# Display.net
KiCad netlist of a schematic drawn in Altium Designer
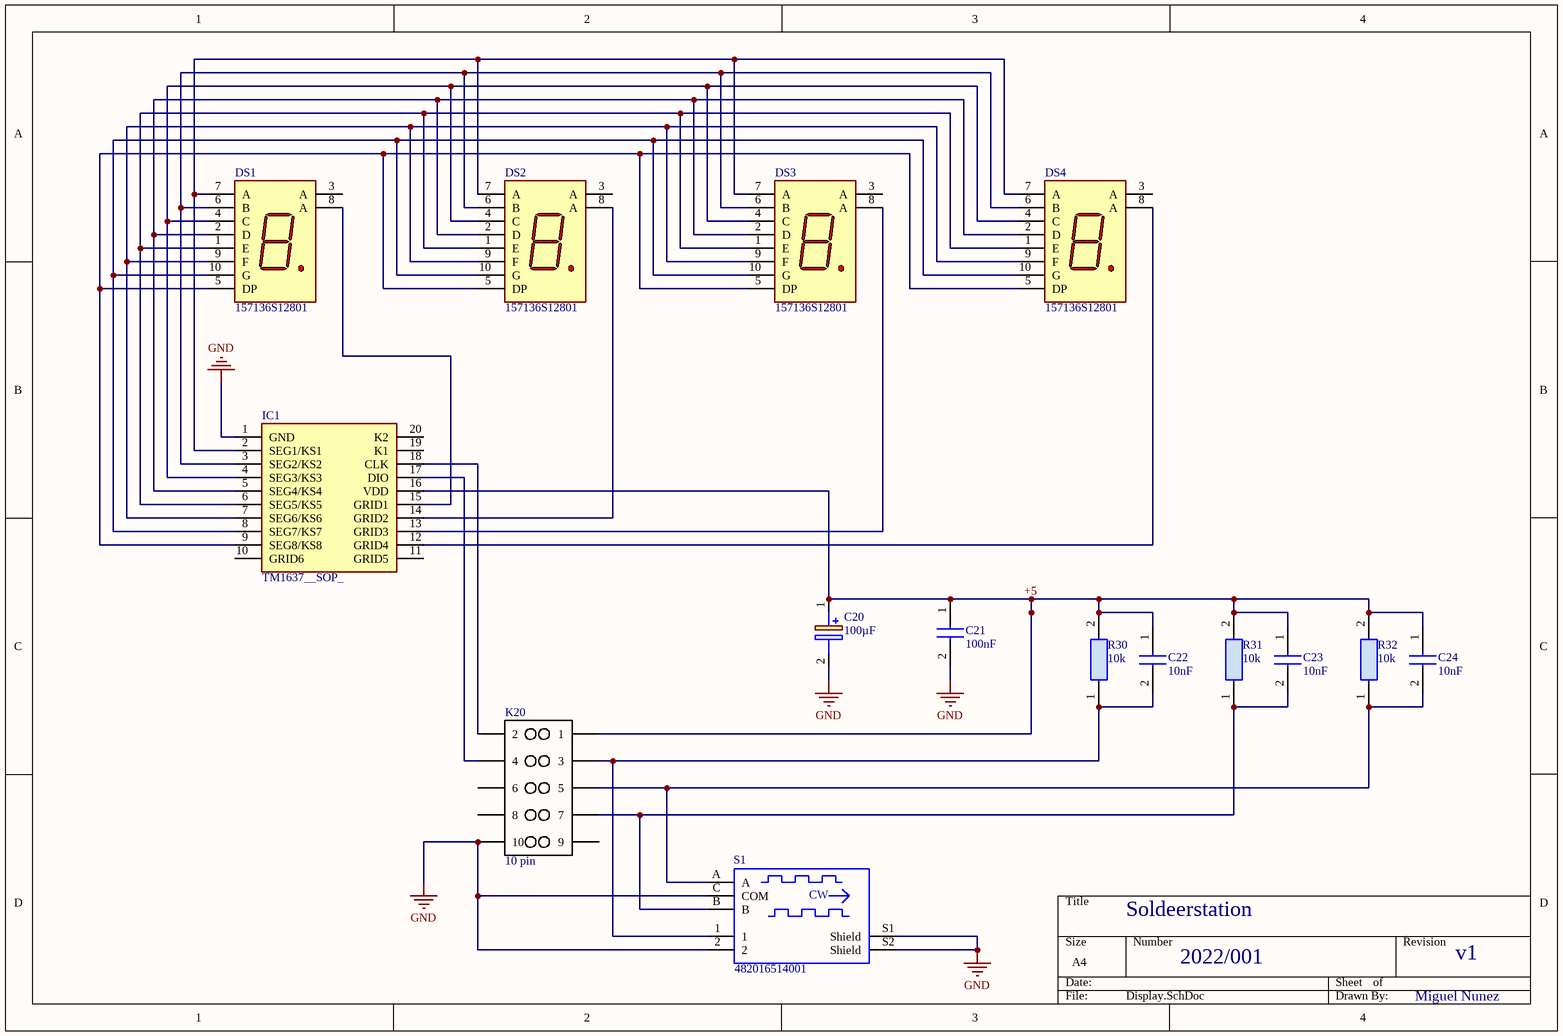
[diagram p0: Display.SchDoc]

(export (version "E")
  (design (tool "Eeschema 10.0.6"))
  (components
    (comp (ref "C20")
      (value "100µF")
      (footprint "WCAP-AT1H_D10H16")
      (description "Capacitor Polarised 100µF Wurth 860241181006")
      (fields (field (name "MANUFACTURER_PART_NUMBER") "860241181006"))
      (libsource (lib "PO_SS_Lib") (part "ELCAP 100µF"))
    )
    (comp (ref "C21")
      (value "100nF")
      (footprint "WCAP-CSGP_0805_L2W1.25H0.8_Reflow")
      (description "Capacitor C0805C104K8RACAUTO")
      (fields (field (name "MANUFACTURER_PART_NUMBER") "C0805C104K8RACAUTO"))
      (libsource (lib "PO_SS_Lib") (part "CAP 0.1µF (100nF)"))
    )
    (comp (ref "C22")
      (value "10nF")
      (footprint "SamacSys:CAPC2012X100N")
      (description "Capacitor C0805C103K1HACAUTO")
      (fields
        (field (name "MOUSER2 PART NUMBER") "80-C0805C103K1HAUTO")
        (field (name "MANUFACTURER_PART_NUMBER") "C0805C103K1HACAUTO")
      )
      (libsource (lib "PO_SS_Lib") (part "CAP 0.01µF (10nF)"))
    )
    (comp (ref "C23")
      (value "10nF")
      (footprint "SamacSys:CAPC2012X100N")
      (description "Capacitor C0805C103K1HACAUTO")
      (fields
        (field (name "MOUSER2 PART NUMBER") "80-C0805C103K1HAUTO")
        (field (name "MANUFACTURER_PART_NUMBER") "C0805C103K1HACAUTO")
      )
      (libsource (lib "PO_SS_Lib") (part "CAP 0.01µF (10nF)"))
    )
    (comp (ref "C24")
      (value "10nF")
      (footprint "SamacSys:CAPC2012X100N")
      (description "Capacitor C0805C103K1HACAUTO")
      (fields
        (field (name "MOUSER2 PART NUMBER") "80-C0805C103K1HAUTO")
        (field (name "MANUFACTURER_PART_NUMBER") "C0805C103K1HACAUTO")
      )
      (libsource (lib "PO_SS_Lib") (part "CAP 0.01µF (10nF)"))
    )
    (comp (ref "DS1")
      (value "157136S12801")
      (footprint "WL-T7DS_L17.5W12.4H7")
      (description "WL-T7DS 7 Segments Display THT Single Digit, Common Anode, 0.52\" / 13.2mm, 38mcd, 2V, Super Red")
      (fields (field (name "MANUFACTURER") "Wurth Elektronik"))
      (libsource (lib "PO_SS_Lib") (part "157136S12801"))
    )
    (comp (ref "DS2")
      (value "157136S12801")
      (footprint "WL-T7DS_L17.5W12.4H7")
      (description "WL-T7DS 7 Segments Display THT Single Digit, Common Anode, 0.52\" / 13.2mm, 38mcd, 2V, Super Red")
      (fields (field (name "MANUFACTURER") "Wurth Elektronik"))
      (libsource (lib "PO_SS_Lib") (part "157136S12801"))
    )
    (comp (ref "DS3")
      (value "157136S12801")
      (footprint "WL-T7DS_L17.5W12.4H7")
      (description "WL-T7DS 7 Segments Display THT Single Digit, Common Anode, 0.52\" / 13.2mm, 38mcd, 2V, Super Red")
      (fields (field (name "MANUFACTURER") "Wurth Elektronik"))
      (libsource (lib "PO_SS_Lib") (part "157136S12801"))
    )
    (comp (ref "DS4")
      (value "157136S12801")
      (footprint "WL-T7DS_L17.5W12.4H7")
      (description "WL-T7DS 7 Segments Display THT Single Digit, Common Anode, 0.52\" / 13.2mm, 38mcd, 2V, Super Red")
      (fields (field (name "MANUFACTURER") "Wurth Elektronik"))
      (libsource (lib "PO_SS_Lib") (part "157136S12801"))
    )
    (comp (ref "IC1")
      (value "TM1637__SOP_")
      (footprint "SamacSys:SOIC127P1045X280-20N")
      (description "Integrated Circuit")
      (fields (field (name "MANUFACTURER_PART_NUMBER") "TM1637 (SOP)"))
      (libsource (lib "PO_SS_Lib") (part "TM1637__SOP_"))
    )
    (comp (ref "K20")
      (value "10 pin")
      (footprint "215307-5_TYC")
      (description "Header, 5-Pin, Dual row")
      (fields (field (name "PUBLISHER") "Altium Limited"))
      (libsource (lib "PO_SS_Lib") (part "Header 2x5"))
    )
    (comp (ref "R30")
      (value "10k")
      (footprint "SamacSys:RESC2012X60N")
      (description "10k SMD 0805  CR0805-FX-1002ELF")
      (fields
        (field (name "MOUSER2 PART NUMBER") "652-CR0805FX-1002ELF")
        (field (name "MANUFACTURER_PART_NUMBER") "CR0805-FX-1002ELF")
      )
      (libsource (lib "PO_SS_Lib") (part "RES 10k 0805"))
    )
    (comp (ref "R31")
      (value "10k")
      (footprint "SamacSys:RESC2012X60N")
      (description "10k SMD 0805  CR0805-FX-1002ELF")
      (fields
        (field (name "MOUSER2 PART NUMBER") "652-CR0805FX-1002ELF")
        (field (name "MANUFACTURER_PART_NUMBER") "CR0805-FX-1002ELF")
      )
      (libsource (lib "PO_SS_Lib") (part "RES 10k 0805"))
    )
    (comp (ref "R32")
      (value "10k")
      (footprint "SamacSys:RESC2012X60N")
      (description "10k SMD 0805  CR0805-FX-1002ELF")
      (fields
        (field (name "MOUSER2 PART NUMBER") "652-CR0805FX-1002ELF")
        (field (name "MANUFACTURER_PART_NUMBER") "CR0805-FX-1002ELF")
      )
      (libsource (lib "PO_SS_Lib") (part "RES 10k 0805"))
    )
    (comp (ref "S1")
      (value "482016514001")
      (footprint "4820xx514001")
      (fields (field (name "MANUFACTURER") "Wurth Elektronik"))
      (libsource (lib "PO_SS_Lib") (part "482016514001"))
    )
  )
  (nets
    (net (code "1") (name "+5") (class "Default")
      (node (ref "C20") (pin "1") (pinfunction "+_1") (pintype "passive"))
      (node (ref "C21") (pin "1") (pinfunction "1_1") (pintype "passive"))
      (node (ref "C22") (pin "1") (pinfunction "1_1") (pintype "passive"))
      (node (ref "C23") (pin "1") (pinfunction "1_1") (pintype "passive"))
      (node (ref "C24") (pin "1") (pinfunction "1_1") (pintype "passive"))
      (node (ref "IC1") (pin "16") (pinfunction "VDD_16") (pintype "passive"))
      (node (ref "K20") (pin "1") (pinfunction "1_1") (pintype "passive"))
      (node (ref "R30") (pin "2") (pinfunction "2_2") (pintype "passive"))
      (node (ref "R31") (pin "2") (pinfunction "2_2") (pintype "passive"))
      (node (ref "R32") (pin "2") (pinfunction "2_2") (pintype "passive"))
    )
    (net (code "2") (name "GND") (class "Default")
      (node (ref "C20") (pin "2") (pinfunction "-_2") (pintype "passive"))
      (node (ref "C21") (pin "2") (pinfunction "2_2") (pintype "passive"))
      (node (ref "IC1") (pin "1") (pinfunction "GND_1") (pintype "passive"))
      (node (ref "K20") (pin "10") (pinfunction "10_10") (pintype "passive"))
      (node (ref "S1") (pin "2") (pinfunction "2_2") (pintype "passive"))
      (node (ref "S1") (pin "C") (pinfunction "COM_C") (pintype "passive"))
      (node (ref "S1") (pin "S1") (pinfunction "Shield_S1") (pintype "passive"))
      (node (ref "S1") (pin "S2") (pinfunction "Shield_S2") (pintype "passive"))
    )
    (net (code "3") (name "Net-(C22-Pad2)") (class "Default")
      (node (ref "C22") (pin "2") (pinfunction "2_2") (pintype "passive"))
      (node (ref "K20") (pin "3") (pinfunction "3_3") (pintype "passive"))
      (node (ref "R30") (pin "1") (pinfunction "1_1") (pintype "passive"))
      (node (ref "S1") (pin "1") (pinfunction "1_1") (pintype "passive"))
    )
    (net (code "4") (name "Net-(C23-Pad2)") (class "Default")
      (node (ref "C23") (pin "2") (pinfunction "2_2") (pintype "passive"))
      (node (ref "K20") (pin "7") (pinfunction "7_7") (pintype "passive"))
      (node (ref "R31") (pin "1") (pinfunction "1_1") (pintype "passive"))
      (node (ref "S1") (pin "B") (pinfunction "B_B") (pintype "passive"))
    )
    (net (code "5") (name "Net-(C24-Pad2)") (class "Default")
      (node (ref "C24") (pin "2") (pinfunction "2_2") (pintype "passive"))
      (node (ref "K20") (pin "5") (pinfunction "5_5") (pintype "passive"))
      (node (ref "R32") (pin "1") (pinfunction "1_1") (pintype "passive"))
      (node (ref "S1") (pin "A") (pinfunction "A_A") (pintype "passive"))
    )
    (net (code "6") (name "Net-(DS1-B)") (class "Default")
      (node (ref "DS1") (pin "6") (pinfunction "B_6") (pintype "passive"))
      (node (ref "DS2") (pin "6") (pinfunction "B_6") (pintype "passive"))
      (node (ref "DS3") (pin "6") (pinfunction "B_6") (pintype "passive"))
      (node (ref "DS4") (pin "6") (pinfunction "B_6") (pintype "passive"))
      (node (ref "IC1") (pin "3") (pinfunction "SEG2/KS2_3") (pintype "passive"))
    )
    (net (code "7") (name "Net-(DS1-C)") (class "Default")
      (node (ref "DS1") (pin "4") (pinfunction "C_4") (pintype "passive"))
      (node (ref "DS2") (pin "4") (pinfunction "C_4") (pintype "passive"))
      (node (ref "DS3") (pin "4") (pinfunction "C_4") (pintype "passive"))
      (node (ref "DS4") (pin "4") (pinfunction "C_4") (pintype "passive"))
      (node (ref "IC1") (pin "4") (pinfunction "SEG3/KS3_4") (pintype "passive"))
    )
    (net (code "8") (name "Net-(DS1-D)") (class "Default")
      (node (ref "DS1") (pin "2") (pinfunction "D_2") (pintype "passive"))
      (node (ref "DS2") (pin "2") (pinfunction "D_2") (pintype "passive"))
      (node (ref "DS3") (pin "2") (pinfunction "D_2") (pintype "passive"))
      (node (ref "DS4") (pin "2") (pinfunction "D_2") (pintype "passive"))
      (node (ref "IC1") (pin "5") (pinfunction "SEG4/KS4_5") (pintype "passive"))
    )
    (net (code "9") (name "Net-(DS1-DP)") (class "Default")
      (node (ref "DS1") (pin "5") (pinfunction "DP_5") (pintype "passive"))
      (node (ref "DS2") (pin "5") (pinfunction "DP_5") (pintype "passive"))
      (node (ref "DS3") (pin "5") (pinfunction "DP_5") (pintype "passive"))
      (node (ref "DS4") (pin "5") (pinfunction "DP_5") (pintype "passive"))
      (node (ref "IC1") (pin "9") (pinfunction "SEG8/KS8_9") (pintype "passive"))
    )
    (net (code "10") (name "Net-(DS1-E)") (class "Default")
      (node (ref "DS1") (pin "1") (pinfunction "E_1") (pintype "passive"))
      (node (ref "DS2") (pin "1") (pinfunction "E_1") (pintype "passive"))
      (node (ref "DS3") (pin "1") (pinfunction "E_1") (pintype "passive"))
      (node (ref "DS4") (pin "1") (pinfunction "E_1") (pintype "passive"))
      (node (ref "IC1") (pin "6") (pinfunction "SEG5/KS5_6") (pintype "passive"))
    )
    (net (code "11") (name "Net-(DS1-F)") (class "Default")
      (node (ref "DS1") (pin "9") (pinfunction "F_9") (pintype "passive"))
      (node (ref "DS2") (pin "9") (pinfunction "F_9") (pintype "passive"))
      (node (ref "DS3") (pin "9") (pinfunction "F_9") (pintype "passive"))
      (node (ref "DS4") (pin "9") (pinfunction "F_9") (pintype "passive"))
      (node (ref "IC1") (pin "7") (pinfunction "SEG6/KS6_7") (pintype "passive"))
    )
    (net (code "12") (name "Net-(DS1-G)") (class "Default")
      (node (ref "DS1") (pin "10") (pinfunction "G_10") (pintype "passive"))
      (node (ref "DS2") (pin "10") (pinfunction "G_10") (pintype "passive"))
      (node (ref "DS3") (pin "10") (pinfunction "G_10") (pintype "passive"))
      (node (ref "DS4") (pin "10") (pinfunction "G_10") (pintype "passive"))
      (node (ref "IC1") (pin "8") (pinfunction "SEG7/KS7_8") (pintype "passive"))
    )
    (net (code "13") (name "Net-(IC1-CLK)") (class "Default")
      (node (ref "IC1") (pin "18") (pinfunction "CLK_18") (pintype "passive"))
      (node (ref "K20") (pin "2") (pinfunction "2_2") (pintype "passive"))
    )
    (net (code "14") (name "Net-(IC1-DIO)") (class "Default")
      (node (ref "IC1") (pin "17") (pinfunction "DIO_17") (pintype "passive"))
      (node (ref "K20") (pin "4") (pinfunction "4_4") (pintype "passive"))
    )
    (net (code "15") (name "Net-(IC1-GRID1)") (class "Default")
      (node (ref "DS1") (pin "8") (pinfunction "A_8") (pintype "passive"))
      (node (ref "IC1") (pin "15") (pinfunction "GRID1_15") (pintype "passive"))
    )
    (net (code "16") (name "Net-(IC1-GRID2)") (class "Default")
      (node (ref "DS2") (pin "8") (pinfunction "A_8") (pintype "passive"))
      (node (ref "IC1") (pin "14") (pinfunction "GRID2_14") (pintype "passive"))
    )
    (net (code "17") (name "Net-(IC1-GRID3)") (class "Default")
      (node (ref "DS3") (pin "8") (pinfunction "A_8") (pintype "passive"))
      (node (ref "IC1") (pin "13") (pinfunction "GRID3_13") (pintype "passive"))
    )
    (net (code "18") (name "Net-(IC1-GRID4)") (class "Default")
      (node (ref "DS4") (pin "8") (pinfunction "A_8") (pintype "passive"))
      (node (ref "IC1") (pin "12") (pinfunction "GRID4_12") (pintype "passive"))
    )
    (net (code "19") (name "Net-(IC1-SEG1{slash}KS1)") (class "Default")
      (node (ref "DS1") (pin "7") (pinfunction "A_7") (pintype "passive"))
      (node (ref "DS2") (pin "7") (pinfunction "A_7") (pintype "passive"))
      (node (ref "DS3") (pin "7") (pinfunction "A_7") (pintype "passive"))
      (node (ref "DS4") (pin "7") (pinfunction "A_7") (pintype "passive"))
      (node (ref "IC1") (pin "2") (pinfunction "SEG1/KS1_2") (pintype "passive"))
    )
    (net (code "20") (name "unconnected-(DS1-A-Pad3)") (class "Default")
      (node (ref "DS1") (pin "3") (pinfunction "A_3") (pintype "passive"))
    )
    (net (code "21") (name "unconnected-(DS2-A-Pad3)") (class "Default")
      (node (ref "DS2") (pin "3") (pinfunction "A_3") (pintype "passive"))
    )
    (net (code "22") (name "unconnected-(DS3-A-Pad3)") (class "Default")
      (node (ref "DS3") (pin "3") (pinfunction "A_3") (pintype "passive"))
    )
    (net (code "23") (name "unconnected-(DS4-A-Pad3)") (class "Default")
      (node (ref "DS4") (pin "3") (pinfunction "A_3") (pintype "passive"))
    )
    (net (code "24") (name "unconnected-(IC1-GRID5-Pad11)") (class "Default")
      (node (ref "IC1") (pin "11") (pinfunction "GRID5_11") (pintype "passive"))
    )
    (net (code "25") (name "unconnected-(IC1-GRID6-Pad10)") (class "Default")
      (node (ref "IC1") (pin "10") (pinfunction "GRID6_10") (pintype "passive"))
    )
    (net (code "26") (name "unconnected-(IC1-K1-Pad19)") (class "Default")
      (node (ref "IC1") (pin "19") (pinfunction "K1_19") (pintype "passive"))
    )
    (net (code "27") (name "unconnected-(IC1-K2-Pad20)") (class "Default")
      (node (ref "IC1") (pin "20") (pinfunction "K2_20") (pintype "passive"))
    )
    (net (code "28") (name "unconnected-(K20-Pad6)") (class "Default")
      (node (ref "K20") (pin "6") (pinfunction "6_6") (pintype "passive"))
    )
    (net (code "29") (name "unconnected-(K20-Pad8)") (class "Default")
      (node (ref "K20") (pin "8") (pinfunction "8_8") (pintype "passive"))
    )
    (net (code "30") (name "unconnected-(K20-Pad9)") (class "Default")
      (node (ref "K20") (pin "9") (pinfunction "9_9") (pintype "passive"))
    )
  )
)
